# capacitor-tester_v0_0_1.net
KiCad netlist of a schematic drawn in EAGLE
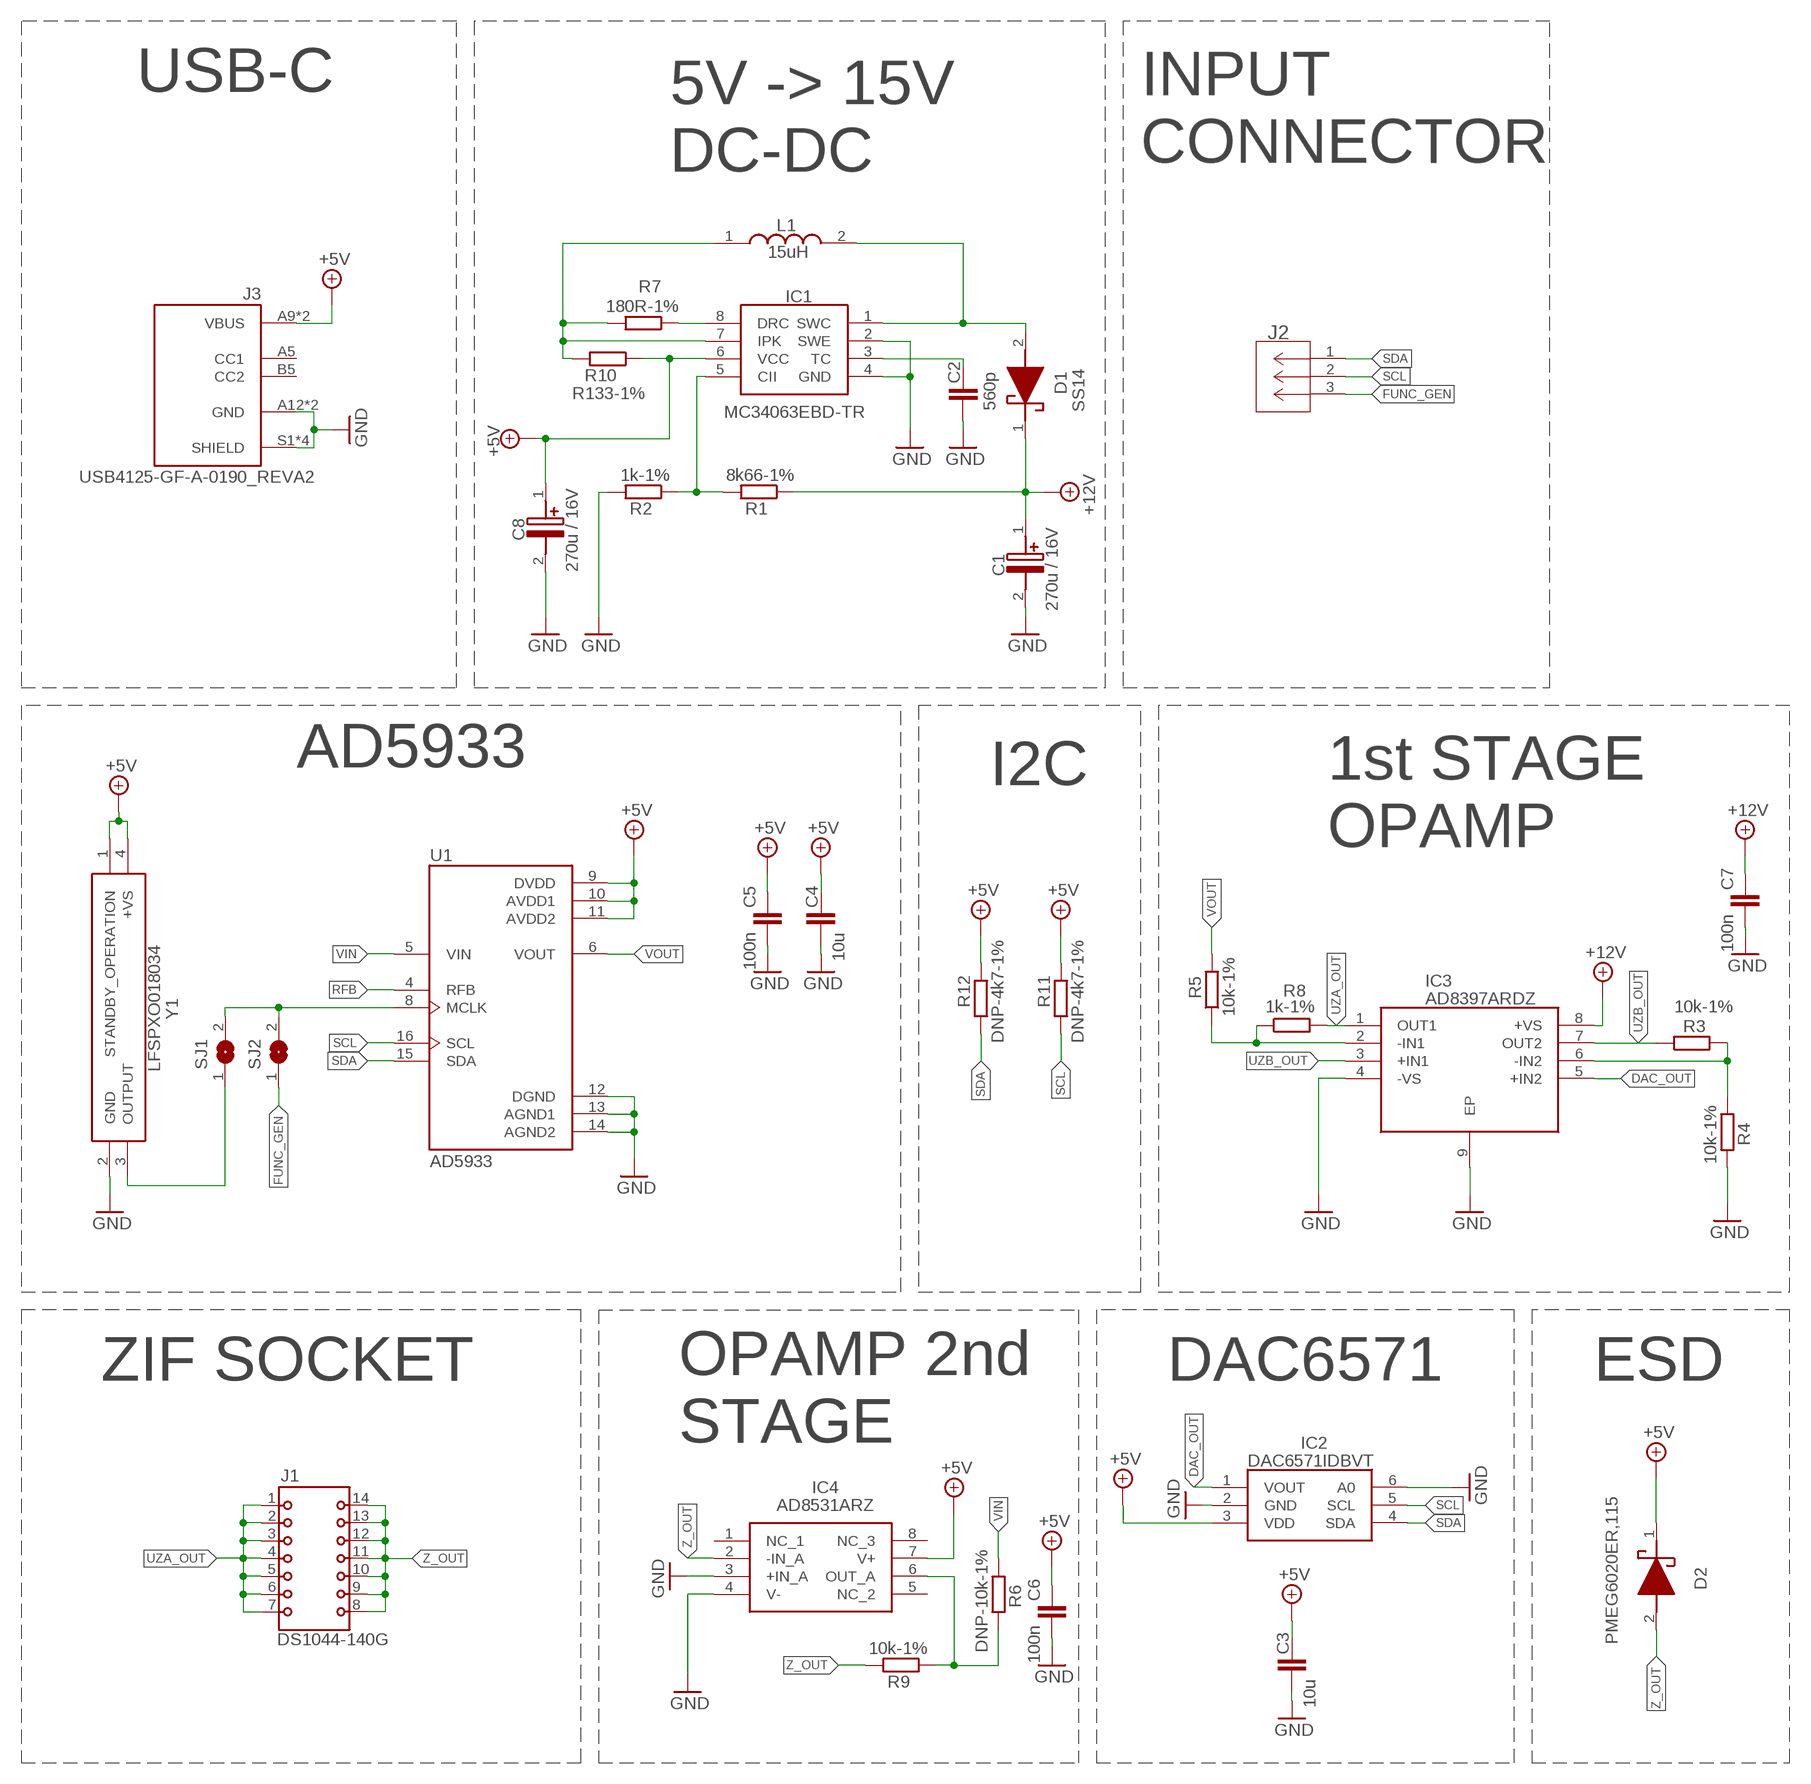
[diagram p0: schematic, sheet 1]

(export (version "E")
  (design (tool "Eeschema 10.0.6"))
  (components
    (comp (ref "C1")
      (value "270u / 16V")
      (footprint "eagle-import:EEE0JA331XP")
      (fields (field (name "MANUFACTURER_PART_NUMBER") "EEEFKC271XSP"))
      (libsource (lib "eagle-import") (part "EEEFKC271XSP"))
    )
    (comp (ref "C2")
      (value "560p")
      (footprint "eagle-import:C0603")
      (libsource (lib "eagle-import") (part "CAPACITOR_SMD_CERAMIC0603"))
    )
    (comp (ref "C3")
      (value "10u")
      (footprint "eagle-import:C0603")
      (libsource (lib "eagle-import") (part "CAPACITOR_SMD_CERAMIC0603"))
    )
    (comp (ref "C4")
      (value "10u")
      (footprint "eagle-import:C0603")
      (libsource (lib "eagle-import") (part "CAPACITOR_SMD_CERAMIC0603"))
    )
    (comp (ref "C5")
      (value "100n")
      (footprint "eagle-import:C0603")
      (libsource (lib "eagle-import") (part "CAPACITOR_SMD_CERAMIC0603"))
    )
    (comp (ref "C6")
      (value "100n")
      (footprint "eagle-import:C0603")
      (libsource (lib "eagle-import") (part "CAPACITOR_SMD_CERAMIC0603"))
    )
    (comp (ref "C7")
      (value "100n")
      (footprint "eagle-import:C0603")
      (libsource (lib "eagle-import") (part "CAPACITOR_SMD_CERAMIC0603"))
    )
    (comp (ref "C8")
      (value "270u / 16V")
      (footprint "eagle-import:EEE0JA331XP")
      (fields (field (name "MANUFACTURER_PART_NUMBER") "EEEFKC271XSP"))
      (libsource (lib "eagle-import") (part "EEEFKC271XSP"))
    )
    (comp (ref "D1")
      (value "SS14")
      (footprint "eagle-import:DIOM5227X270N")
      (fields (field (name "MOUSER_PART_NUMBER") "512-SS14"))
      (libsource (lib "eagle-import") (part "SS14"))
    )
    (comp (ref "D2")
      (value "PMEG6020ER,115")
      (footprint "eagle-import:PMEG6020ER115")
      (libsource (lib "eagle-import") (part "PMEG6020ER,115"))
    )
    (comp (ref "IC1")
      (value "MC34063EBD-TR")
      (footprint "eagle-import:SOIC127P600X175-8N")
      (libsource (lib "eagle-import") (part "MC34063EBD-TR"))
    )
    (comp (ref "IC2")
      (value "DAC6571IDBVT")
      (footprint "eagle-import:SOT95P280X145-6N")
      (fields (field (name "MOUSER_PART_NUMBER") "595-DAC6571IDBVT"))
      (libsource (lib "eagle-import") (part "DAC6571IDBVT"))
    )
    (comp (ref "IC3")
      (value "AD8397ARDZ")
      (footprint "eagle-import:SOIC127P600X175-9N")
      (fields (field (name "MOUSER_PART_NUMBER") "584-AD8397ARDZ"))
      (libsource (lib "eagle-import") (part "AD8397ARDZ"))
    )
    (comp (ref "IC4")
      (value "AD8531ARZ")
      (footprint "eagle-import:SOIC127P600X175-8N")
      (fields (field (name "MOUSER_PART_NUMBER") "584-AD8531ARZ"))
      (libsource (lib "eagle-import") (part "AD8531ARZ"))
    )
    (comp (ref "J1")
      (value "DS1044-140G")
      (footprint "eagle-import:CONNFLY_DS1044-140G")
      (fields (field (name "MF") "Connfly"))
      (libsource (lib "eagle-import") (part "DS1044-140G"))
    )
    (comp (ref "J2")
      (value "250-103")
      (footprint "eagle-import:CONN3_250-103_WAG")
      (fields (field (name "COPYRIGHT") "Copyright (C) 2025 Ultra Librarian. All rights reserved."))
      (libsource (lib "eagle-import") (part "250-103"))
    )
    (comp (ref "J3")
      (value "USB4125-GF-A-0190_REVA2")
      (footprint "eagle-import:GCT_USB4125-GF-A-0190_REVA2")
      (fields (field (name "MF") "Global Connector Technology") (field (name "MP") "USB4125-GF-A-0190"))
      (libsource (lib "eagle-import") (part "USB4125-GF-A-0190_REVA2"))
    )
    (comp (ref "L1")
      (value "15uH")
      (footprint "eagle-import:SDR0604330KL")
      (fields (field (name "MANUFACTURER_PART_NUMBER") "SDR0604-150YL"))
      (libsource (lib "eagle-import") (part "SDR0604-150YL"))
    )
    (comp (ref "R1")
      (value "8k66-1%")
      (footprint "eagle-import:R0603")
      (libsource (lib "eagle-import") (part "RESISTOR_SMD0603"))
    )
    (comp (ref "R2")
      (value "1k-1%")
      (footprint "eagle-import:R0603")
      (libsource (lib "eagle-import") (part "RESISTOR_SMD0603"))
    )
    (comp (ref "R3")
      (value "10k-1%")
      (footprint "eagle-import:R0603")
      (libsource (lib "eagle-import") (part "RESISTOR_SMD0603"))
    )
    (comp (ref "R4")
      (value "10k-1%")
      (footprint "eagle-import:R0603")
      (libsource (lib "eagle-import") (part "RESISTOR_SMD0603"))
    )
    (comp (ref "R5")
      (value "10k-1%")
      (footprint "eagle-import:R0603")
      (libsource (lib "eagle-import") (part "RESISTOR_SMD0603"))
    )
    (comp (ref "R6")
      (value "DNP-10k-1%")
      (footprint "eagle-import:R0603")
      (libsource (lib "eagle-import") (part "RESISTOR_SMD0603"))
    )
    (comp (ref "R7")
      (value "180R-1%")
      (footprint "eagle-import:R0603")
      (libsource (lib "eagle-import") (part "RESISTOR_SMD0603"))
    )
    (comp (ref "R8")
      (value "1k-1%")
      (footprint "eagle-import:R0603")
      (libsource (lib "eagle-import") (part "RESISTOR_SMD0603"))
    )
    (comp (ref "R9")
      (value "10k-1%")
      (footprint "eagle-import:R0603")
      (libsource (lib "eagle-import") (part "RESISTOR_SMD0603"))
    )
    (comp (ref "R10")
      (value "R133-1%")
      (footprint "eagle-import:R0603")
      (libsource (lib "eagle-import") (part "RESISTOR_SMD0603"))
    )
    (comp (ref "R11")
      (value "DNP-4k7-1%")
      (footprint "eagle-import:R0603")
      (libsource (lib "eagle-import") (part "RESISTOR_SMD0603"))
    )
    (comp (ref "R12")
      (value "DNP-4k7-1%")
      (footprint "eagle-import:R0603")
      (libsource (lib "eagle-import") (part "RESISTOR_SMD0603"))
    )
    (comp (ref "SJ1")
      (value "SJW")
      (footprint "eagle-import:SJW")
      (libsource (lib "eagle-import") (part "SJW"))
    )
    (comp (ref "SJ2")
      (value "SJW")
      (footprint "eagle-import:SJW")
      (libsource (lib "eagle-import") (part "SJW"))
    )
    (comp (ref "U1")
      (value "AD5933")
      (footprint "eagle-import:SOP65P780X200-16N")
      (fields (field (name "MF") "Analog Devices, Inc."))
      (libsource (lib "eagle-import") (part "AD5933"))
    )
    (comp (ref "Y1")
      (value "LFSPXO018034")
      (footprint "eagle-import:LFSPXO018034")
      (fields (field (name "MOUSER_PART_NUMBER") "449-LFSPXO018034"))
      (libsource (lib "eagle-import") (part "LFSPXO018034"))
    )
  )
  (nets
    (net (code "1") (name "+5V") (class "Default")
      (node (ref "C3") (pin "1") (pinfunction "1_1") (pintype "passive"))
      (node (ref "C4") (pin "1") (pinfunction "1_1") (pintype "passive"))
      (node (ref "C5") (pin "1") (pinfunction "1_1") (pintype "passive"))
      (node (ref "C6") (pin "1") (pinfunction "1_1") (pintype "passive"))
      (node (ref "C8") (pin "1") (pinfunction "+_1") (pintype "bidirectional"))
      (node (ref "D2") (pin "1") (pinfunction "K_1") (pintype "bidirectional"))
      (node (ref "IC1") (pin "6") (pinfunction "VCC_6") (pintype "power_in"))
      (node (ref "IC2") (pin "3") (pinfunction "VDD_3") (pintype "bidirectional"))
      (node (ref "IC4") (pin "7") (pinfunction "V+_7") (pintype "bidirectional"))
      (node (ref "J3") (pin "A9") (pinfunction "VBUS_A9") (pintype "power_in"))
      (node (ref "J3") (pin "B9") (pinfunction "VBUS_B9") (pintype "power_in"))
      (node (ref "R10") (pin "1") (pinfunction "1_1") (pintype "passive"))
      (node (ref "R11") (pin "2") (pinfunction "2_2") (pintype "passive"))
      (node (ref "R12") (pin "2") (pinfunction "2_2") (pintype "passive"))
      (node (ref "U1") (pin "10") (pinfunction "AVDD1_10") (pintype "power_in"))
      (node (ref "U1") (pin "11") (pinfunction "AVDD2_11") (pintype "power_in"))
      (node (ref "U1") (pin "9") (pinfunction "DVDD_9") (pintype "power_in"))
      (node (ref "Y1") (pin "1") (pinfunction "STANDBY_OPERATION_1") (pintype "bidirectional"))
      (node (ref "Y1") (pin "4") (pinfunction "+VS_4") (pintype "bidirectional"))
    )
    (net (code "2") (name "+12V") (class "Default")
      (node (ref "C1") (pin "1") (pinfunction "+_1") (pintype "bidirectional"))
      (node (ref "C7") (pin "1") (pinfunction "1_1") (pintype "passive"))
      (node (ref "D1") (pin "1") (pinfunction "K_1") (pintype "bidirectional"))
      (node (ref "IC3") (pin "8") (pinfunction "+VS_8") (pintype "bidirectional"))
      (node (ref "R1") (pin "1") (pinfunction "1_1") (pintype "passive"))
    )
    (net (code "3") (name "DAC_OUT") (class "Default")
      (node (ref "IC2") (pin "1") (pinfunction "VOUT_1") (pintype "bidirectional"))
      (node (ref "IC3") (pin "5") (pinfunction "+IN2_5") (pintype "bidirectional"))
    )
    (net (code "4") (name "FUNC_GEN") (class "Default")
      (node (ref "J2") (pin "3") (pinfunction "3_3") (pintype "passive"))
      (node (ref "SJ2") (pin "1") (pinfunction "1_1") (pintype "passive"))
    )
    (net (code "5") (name "GND") (class "Default")
      (node (ref "C1") (pin "2") (pinfunction "-_2") (pintype "bidirectional"))
      (node (ref "C2") (pin "2") (pinfunction "2_2") (pintype "passive"))
      (node (ref "C3") (pin "2") (pinfunction "2_2") (pintype "passive"))
      (node (ref "C4") (pin "2") (pinfunction "2_2") (pintype "passive"))
      (node (ref "C5") (pin "2") (pinfunction "2_2") (pintype "passive"))
      (node (ref "C6") (pin "2") (pinfunction "2_2") (pintype "passive"))
      (node (ref "C7") (pin "2") (pinfunction "2_2") (pintype "passive"))
      (node (ref "C8") (pin "2") (pinfunction "-_2") (pintype "bidirectional"))
      (node (ref "IC1") (pin "2") (pinfunction "SWE_2") (pintype "bidirectional"))
      (node (ref "IC1") (pin "4") (pinfunction "GND_4") (pintype "power_in"))
      (node (ref "IC2") (pin "2") (pinfunction "GND_2") (pintype "bidirectional"))
      (node (ref "IC2") (pin "6") (pinfunction "A0_6") (pintype "bidirectional"))
      (node (ref "IC3") (pin "4") (pinfunction "-VS_4") (pintype "bidirectional"))
      (node (ref "IC3") (pin "9") (pinfunction "EP_9") (pintype "bidirectional"))
      (node (ref "IC4") (pin "3") (pinfunction "+IN_A_3") (pintype "bidirectional"))
      (node (ref "IC4") (pin "4") (pinfunction "V-_4") (pintype "bidirectional"))
      (node (ref "J3") (pin "A12") (pinfunction "GND_A12") (pintype "power_in"))
      (node (ref "J3") (pin "B12") (pinfunction "GND_B12") (pintype "power_in"))
      (node (ref "J3") (pin "S1") (pinfunction "SHIELD_S1") (pintype "passive"))
      (node (ref "J3") (pin "S2") (pinfunction "SHIELD_S2") (pintype "passive"))
      (node (ref "J3") (pin "S3") (pinfunction "SHIELD_S3") (pintype "passive"))
      (node (ref "J3") (pin "S4") (pinfunction "SHIELD_S4") (pintype "passive"))
      (node (ref "R2") (pin "2") (pinfunction "2_2") (pintype "passive"))
      (node (ref "R4") (pin "2") (pinfunction "2_2") (pintype "passive"))
      (node (ref "U1") (pin "12") (pinfunction "DGND_12") (pintype "power_in"))
      (node (ref "U1") (pin "13") (pinfunction "AGND1_13") (pintype "power_in"))
      (node (ref "U1") (pin "14") (pinfunction "AGND2_14") (pintype "power_in"))
      (node (ref "Y1") (pin "2") (pinfunction "GND_2") (pintype "bidirectional"))
    )
    (net (code "6") (name "Net-(D1-A)") (class "Default")
      (node (ref "D1") (pin "2") (pinfunction "A_2") (pintype "bidirectional"))
      (node (ref "IC1") (pin "1") (pinfunction "SWC_1") (pintype "bidirectional"))
      (node (ref "L1") (pin "2") (pinfunction "2_2") (pintype "bidirectional"))
    )
    (net (code "7") (name "Net-(IC1-CII)") (class "Default")
      (node (ref "IC1") (pin "5") (pinfunction "CII_5") (pintype "bidirectional"))
      (node (ref "R1") (pin "2") (pinfunction "2_2") (pintype "passive"))
      (node (ref "R2") (pin "1") (pinfunction "1_1") (pintype "passive"))
    )
    (net (code "8") (name "Net-(IC1-DRC)") (class "Default")
      (node (ref "IC1") (pin "8") (pinfunction "DRC_8") (pintype "bidirectional"))
      (node (ref "R7") (pin "1") (pinfunction "1_1") (pintype "passive"))
    )
    (net (code "9") (name "Net-(IC1-IPK)") (class "Default")
      (node (ref "IC1") (pin "7") (pinfunction "IPK_7") (pintype "bidirectional"))
      (node (ref "L1") (pin "1") (pinfunction "1_1") (pintype "bidirectional"))
      (node (ref "R10") (pin "2") (pinfunction "2_2") (pintype "passive"))
      (node (ref "R7") (pin "2") (pinfunction "2_2") (pintype "passive"))
    )
    (net (code "10") (name "Net-(IC1-TC)") (class "Default")
      (node (ref "C2") (pin "1") (pinfunction "1_1") (pintype "passive"))
      (node (ref "IC1") (pin "3") (pinfunction "TC_3") (pintype "bidirectional"))
    )
    (net (code "11") (name "Net-(IC3--IN1)") (class "Default")
      (node (ref "IC3") (pin "2") (pinfunction "-IN1_2") (pintype "bidirectional"))
      (node (ref "R5") (pin "1") (pinfunction "1_1") (pintype "passive"))
      (node (ref "R8") (pin "1") (pinfunction "1_1") (pintype "passive"))
    )
    (net (code "12") (name "Net-(IC3--IN2)") (class "Default")
      (node (ref "IC3") (pin "6") (pinfunction "-IN2_6") (pintype "bidirectional"))
      (node (ref "R3") (pin "2") (pinfunction "2_2") (pintype "passive"))
      (node (ref "R4") (pin "1") (pinfunction "1_1") (pintype "passive"))
    )
    (net (code "13") (name "Net-(IC4-OUT_A)") (class "Default")
      (node (ref "IC4") (pin "6") (pinfunction "OUT_A_6") (pintype "bidirectional"))
      (node (ref "R6") (pin "2") (pinfunction "2_2") (pintype "passive"))
      (node (ref "R9") (pin "1") (pinfunction "1_1") (pintype "passive"))
    )
    (net (code "14") (name "Net-(U1-MCLK)") (class "Default")
      (node (ref "SJ1") (pin "2") (pinfunction "2_2") (pintype "passive"))
      (node (ref "SJ2") (pin "2") (pinfunction "2_2") (pintype "passive"))
      (node (ref "U1") (pin "8") (pinfunction "MCLK_8") (pintype "input"))
    )
    (net (code "15") (name "Net-(Y1-OUTPUT)") (class "Default")
      (node (ref "SJ1") (pin "1") (pinfunction "1_1") (pintype "passive"))
      (node (ref "Y1") (pin "3") (pinfunction "OUTPUT_3") (pintype "bidirectional"))
    )
    (net (code "16") (name "RFB") (class "Default")
      (node (ref "U1") (pin "4") (pinfunction "RFB_4") (pintype "input"))
    )
    (net (code "17") (name "SCL") (class "Default")
      (node (ref "IC2") (pin "5") (pinfunction "SCL_5") (pintype "bidirectional"))
      (node (ref "J2") (pin "2") (pinfunction "2_2") (pintype "passive"))
      (node (ref "R11") (pin "1") (pinfunction "1_1") (pintype "passive"))
      (node (ref "U1") (pin "16") (pinfunction "SCL_16") (pintype "input"))
    )
    (net (code "18") (name "SDA") (class "Default")
      (node (ref "IC2") (pin "4") (pinfunction "SDA_4") (pintype "bidirectional"))
      (node (ref "J2") (pin "1") (pinfunction "1_1") (pintype "passive"))
      (node (ref "R12") (pin "1") (pinfunction "1_1") (pintype "passive"))
      (node (ref "U1") (pin "15") (pinfunction "SDA_15") (pintype "bidirectional"))
    )
    (net (code "19") (name "UZA_OUT") (class "Default")
      (node (ref "IC3") (pin "1") (pinfunction "OUT1_1") (pintype "bidirectional"))
      (node (ref "J1") (pin "1") (pinfunction "1_1") (pintype "passive"))
      (node (ref "J1") (pin "2") (pinfunction "2_2") (pintype "passive"))
      (node (ref "J1") (pin "3") (pinfunction "3_3") (pintype "passive"))
      (node (ref "J1") (pin "4") (pinfunction "4_4") (pintype "passive"))
      (node (ref "J1") (pin "5") (pinfunction "5_5") (pintype "passive"))
      (node (ref "J1") (pin "6") (pinfunction "6_6") (pintype "passive"))
      (node (ref "J1") (pin "7") (pinfunction "7_7") (pintype "passive"))
      (node (ref "R8") (pin "2") (pinfunction "2_2") (pintype "passive"))
    )
    (net (code "20") (name "UZB_OUT") (class "Default")
      (node (ref "IC3") (pin "3") (pinfunction "+IN1_3") (pintype "bidirectional"))
      (node (ref "IC3") (pin "7") (pinfunction "OUT2_7") (pintype "bidirectional"))
      (node (ref "R3") (pin "1") (pinfunction "1_1") (pintype "passive"))
    )
    (net (code "21") (name "VIN") (class "Default")
      (node (ref "R6") (pin "1") (pinfunction "1_1") (pintype "passive"))
      (node (ref "U1") (pin "5") (pinfunction "VIN_5") (pintype "input"))
    )
    (net (code "22") (name "VOUT") (class "Default")
      (node (ref "R5") (pin "2") (pinfunction "2_2") (pintype "passive"))
      (node (ref "U1") (pin "6") (pinfunction "VOUT_6") (pintype "output"))
    )
    (net (code "23") (name "Z_OUT") (class "Default")
      (node (ref "D2") (pin "2") (pinfunction "A_2") (pintype "bidirectional"))
      (node (ref "IC4") (pin "2") (pinfunction "-IN_A_2") (pintype "bidirectional"))
      (node (ref "J1") (pin "10") (pinfunction "10_10") (pintype "passive"))
      (node (ref "J1") (pin "11") (pinfunction "11_11") (pintype "passive"))
      (node (ref "J1") (pin "12") (pinfunction "12_12") (pintype "passive"))
      (node (ref "J1") (pin "13") (pinfunction "13_13") (pintype "passive"))
      (node (ref "J1") (pin "14") (pinfunction "14_14") (pintype "passive"))
      (node (ref "J1") (pin "8") (pinfunction "8_8") (pintype "passive"))
      (node (ref "J1") (pin "9") (pinfunction "9_9") (pintype "passive"))
      (node (ref "R9") (pin "2") (pinfunction "2_2") (pintype "passive"))
    )
    (net (code "24") (name "unconnected-(IC4-NC_1-Pad1)") (class "Default")
      (node (ref "IC4") (pin "1") (pinfunction "NC_1_1") (pintype "bidirectional"))
    )
    (net (code "25") (name "unconnected-(IC4-NC_2-Pad5)") (class "Default")
      (node (ref "IC4") (pin "5") (pinfunction "NC_2_5") (pintype "bidirectional"))
    )
    (net (code "26") (name "unconnected-(IC4-NC_3-Pad8)") (class "Default")
      (node (ref "IC4") (pin "8") (pinfunction "NC_3_8") (pintype "bidirectional"))
    )
    (net (code "27") (name "unconnected-(J3-CC1-PadA5)") (class "Default")
      (node (ref "J3") (pin "A5") (pinfunction "CC1_A5") (pintype "bidirectional"))
    )
    (net (code "28") (name "unconnected-(J3-CC2-PadB5)") (class "Default")
      (node (ref "J3") (pin "B5") (pinfunction "CC2_B5") (pintype "bidirectional"))
    )
  )
)
